# H7-Battery.net
KiCad netlist of a schematic drawn in Altium Designer
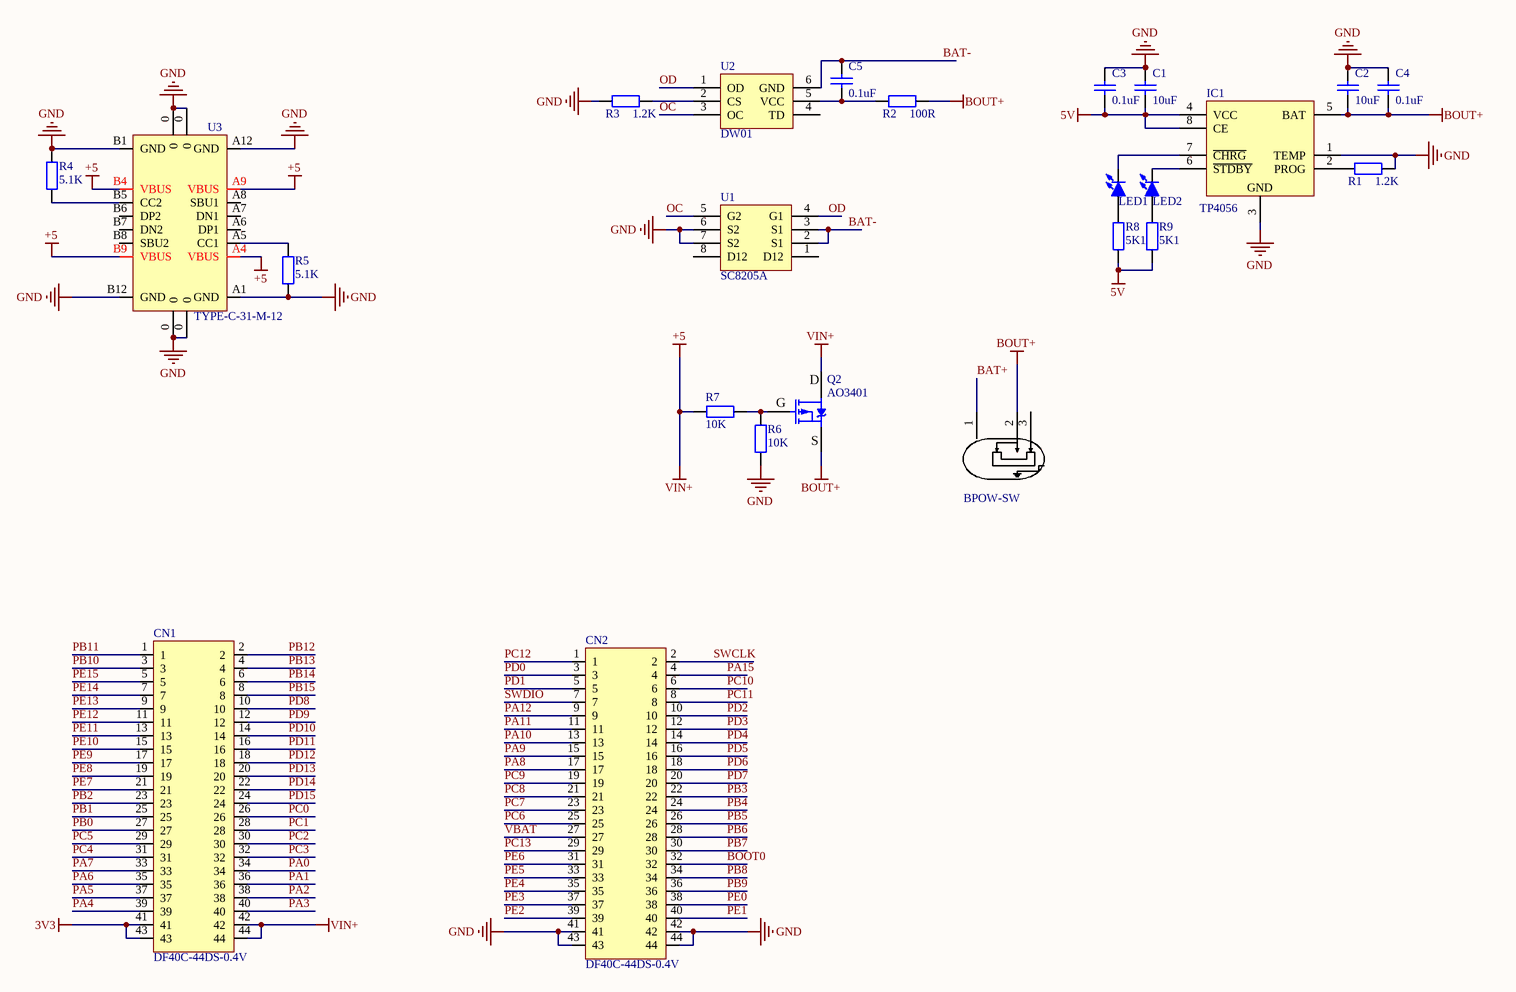
[diagram p0: H7-Battery.SchDoc]

(export (version "E")
  (design (tool "Eeschema 10.0.6"))
  (components
    (comp (ref "BPOW-SW")
      (value "MSK12C02")
      (footprint "SW-TH_MSK12C02")
      (fields (field (name "MANUFACTURER") "SHOU HAN(首韩)"))
      (libsource (lib "Pi") (part "MSK12C02"))
    )
    (comp (ref "C1")
      (value "10uF")
      (footprint "C0603_L")
      (description "贴片电容")
      (libsource (lib "0.1 - 电阻-电容-电感-电位器") (part "C"))
    )
    (comp (ref "C2")
      (value "10uF")
      (footprint "C0603_L")
      (description "贴片电容")
      (libsource (lib "0.1 - 电阻-电容-电感-电位器") (part "C"))
    )
    (comp (ref "C3")
      (value "0.1uF")
      (footprint "C0603_L")
      (description "贴片电容")
      (libsource (lib "0.1 - 电阻-电容-电感-电位器") (part "C"))
    )
    (comp (ref "C4")
      (value "0.1uF")
      (footprint "C0603_L")
      (description "贴片电容")
      (libsource (lib "0.1 - 电阻-电容-电感-电位器") (part "C"))
    )
    (comp (ref "C5")
      (value "0.1uF")
      (footprint "C0603_L")
      (description "贴片电容")
      (libsource (lib "0.1 - 电阻-电容-电感-电位器") (part "C"))
    )
    (comp (ref "CN1")
      (value "DF40C-44DS-0.4V")
      (footprint "DF40C-44DS-0.4V")
      (description "母座")
      (libsource (lib "Pi") (part "DF40C-44DS-0.4V"))
    )
    (comp (ref "CN2")
      (value "DF40C-44DS-0.4V")
      (footprint "DF40C-44DS-0.4V")
      (description "母座")
      (libsource (lib "Pi") (part "DF40C-44DS-0.4V"))
    )
    (comp (ref "IC1")
      (value "TP4056")
      (footprint "ESOP8_L")
      (description "锂电池充电管理")
      (libsource (lib "Pi") (part "TP4056"))
    )
    (comp (ref "LED1")
      (value "~")
      (footprint "LED0603_R")
      (description "贴片LED")
      (libsource (lib "0.3 - LED发光二极管") (part "LED-SMD"))
    )
    (comp (ref "LED2")
      (value "~")
      (footprint "LED0603_G")
      (description "贴片LED")
      (libsource (lib "0.3 - LED发光二极管") (part "LED-SMD"))
    )
    (comp (ref "Q2")
      (value "AO3401")
      (footprint "SOT23-3N")
      (description "P沟道 30V/4.2A")
      (libsource (lib "0.4 - 三极管-场效应管-可控硅") (part "AO3401"))
    )
    (comp (ref "R1")
      (value "1.2K")
      (footprint "R0603_L")
      (description "贴片电阻")
      (libsource (lib "0.1 - 电阻-电容-电感-电位器") (part "R"))
    )
    (comp (ref "R2")
      (value "100R")
      (footprint "R0603_L")
      (description "贴片电阻")
      (libsource (lib "0.1 - 电阻-电容-电感-电位器") (part "R"))
    )
    (comp (ref "R3")
      (value "1.2K")
      (footprint "R0603_L")
      (description "贴片电阻")
      (libsource (lib "0.1 - 电阻-电容-电感-电位器") (part "R"))
    )
    (comp (ref "R4")
      (value "5.1K")
      (footprint "R0603_L")
      (description "贴片电阻")
      (libsource (lib "0.1 - 电阻-电容-电感-电位器") (part "R"))
    )
    (comp (ref "R5")
      (value "5.1K")
      (footprint "R0603_L")
      (description "贴片电阻")
      (libsource (lib "0.1 - 电阻-电容-电感-电位器") (part "R"))
    )
    (comp (ref "R6")
      (value "10K")
      (footprint "R0603_L")
      (description "贴片电阻")
      (libsource (lib "0.1 - 电阻-电容-电感-电位器") (part "R"))
    )
    (comp (ref "R7")
      (value "10K")
      (footprint "R0603_L")
      (description "贴片电阻")
      (libsource (lib "0.1 - 电阻-电容-电感-电位器") (part "R"))
    )
    (comp (ref "R8")
      (value "5K1")
      (footprint "R0603_L")
      (description "贴片电阻")
      (libsource (lib "0.1 - 电阻-电容-电感-电位器") (part "R"))
    )
    (comp (ref "R9")
      (value "5K1")
      (footprint "R0603_L")
      (description "贴片电阻")
      (libsource (lib "0.1 - 电阻-电容-电感-电位器") (part "R"))
    )
    (comp (ref "U1")
      (value "SC8205A")
      (footprint "TSSOP8_L")
      (description "N沟道 6A/20V锂电池保护板用的MOS管")
      (libsource (lib "Pi") (part "SC8205A"))
    )
    (comp (ref "U2")
      (value "DW01")
      (footprint "SOT23-6L")
      (description "锂电池过流保护IC")
      (libsource (lib "Pi") (part "DW01"))
    )
    (comp (ref "U3")
      (value "TYPE-C-31-M-12")
      (footprint "TYPE-C-31-M-12")
      (libsource (lib "Pi") (part "TYPE-C-31-M-12"))
    )
  )
  (nets
    (net (code "1") (name "+5") (class "Default")
      (node (ref "CN1") (pin "42") (pinfunction "42_42") (pintype "passive"))
      (node (ref "CN1") (pin "44") (pinfunction "44_44") (pintype "passive"))
      (node (ref "Q2") (pin "3") (pinfunction "D_3") (pintype "passive"))
      (node (ref "R7") (pin "2") (pinfunction "2_2") (pintype "passive"))
      (node (ref "U3") (pin "A4") (pinfunction "VBUS_A4") (pintype "passive"))
      (node (ref "U3") (pin "A9") (pinfunction "VBUS_A9") (pintype "passive"))
      (node (ref "U3") (pin "B4") (pinfunction "VBUS_B4") (pintype "passive"))
      (node (ref "U3") (pin "B9") (pinfunction "VBUS_B9") (pintype "passive"))
    )
    (net (code "2") (name "/BAT+") (class "Default")
      (node (ref "BPOW-SW") (pin "1") (pinfunction "1_1") (pintype "passive"))
    )
    (net (code "3") (name "/BAT-") (class "Default")
      (node (ref "C5") (pin "2") (pinfunction "2_2") (pintype "passive"))
      (node (ref "U1") (pin "2") (pinfunction "S1_2") (pintype "passive"))
      (node (ref "U1") (pin "3") (pinfunction "S1_3") (pintype "passive"))
      (node (ref "U2") (pin "6") (pinfunction "GND_6") (pintype "passive"))
    )
    (net (code "4") (name "/BOOT0") (class "Default")
      (node (ref "CN2") (pin "32") (pinfunction "32_32") (pintype "passive"))
    )
    (net (code "5") (name "/OC") (class "Default")
      (node (ref "U1") (pin "5") (pinfunction "G2_5") (pintype "passive"))
      (node (ref "U2") (pin "3") (pinfunction "OC_3") (pintype "passive"))
    )
    (net (code "6") (name "/OD") (class "Default")
      (node (ref "U1") (pin "4") (pinfunction "G1_4") (pintype "passive"))
      (node (ref "U2") (pin "1") (pinfunction "OD_1") (pintype "passive"))
    )
    (net (code "7") (name "/PA0") (class "Default")
      (node (ref "CN1") (pin "34") (pinfunction "34_34") (pintype "passive"))
    )
    (net (code "8") (name "/PA1") (class "Default")
      (node (ref "CN1") (pin "36") (pinfunction "36_36") (pintype "passive"))
    )
    (net (code "9") (name "/PA2") (class "Default")
      (node (ref "CN1") (pin "38") (pinfunction "38_38") (pintype "passive"))
    )
    (net (code "10") (name "/PA3") (class "Default")
      (node (ref "CN1") (pin "40") (pinfunction "40_40") (pintype "passive"))
    )
    (net (code "11") (name "/PA4") (class "Default")
      (node (ref "CN1") (pin "39") (pinfunction "39_39") (pintype "passive"))
    )
    (net (code "12") (name "/PA5") (class "Default")
      (node (ref "CN1") (pin "37") (pinfunction "37_37") (pintype "passive"))
    )
    (net (code "13") (name "/PA6") (class "Default")
      (node (ref "CN1") (pin "35") (pinfunction "35_35") (pintype "passive"))
    )
    (net (code "14") (name "/PA7") (class "Default")
      (node (ref "CN1") (pin "33") (pinfunction "33_33") (pintype "passive"))
    )
    (net (code "15") (name "/PA8") (class "Default")
      (node (ref "CN2") (pin "17") (pinfunction "17_17") (pintype "passive"))
    )
    (net (code "16") (name "/PA9") (class "Default")
      (node (ref "CN2") (pin "15") (pinfunction "15_15") (pintype "passive"))
    )
    (net (code "17") (name "/PA10") (class "Default")
      (node (ref "CN2") (pin "13") (pinfunction "13_13") (pintype "passive"))
    )
    (net (code "18") (name "/PA11") (class "Default")
      (node (ref "CN2") (pin "11") (pinfunction "11_11") (pintype "passive"))
    )
    (net (code "19") (name "/PA12") (class "Default")
      (node (ref "CN2") (pin "9") (pinfunction "9_9") (pintype "passive"))
    )
    (net (code "20") (name "/PA15") (class "Default")
      (node (ref "CN2") (pin "4") (pinfunction "4_4") (pintype "passive"))
    )
    (net (code "21") (name "/PB0") (class "Default")
      (node (ref "CN1") (pin "27") (pinfunction "27_27") (pintype "passive"))
    )
    (net (code "22") (name "/PB1") (class "Default")
      (node (ref "CN1") (pin "25") (pinfunction "25_25") (pintype "passive"))
    )
    (net (code "23") (name "/PB2") (class "Default")
      (node (ref "CN1") (pin "23") (pinfunction "23_23") (pintype "passive"))
    )
    (net (code "24") (name "/PB3") (class "Default")
      (node (ref "CN2") (pin "22") (pinfunction "22_22") (pintype "passive"))
    )
    (net (code "25") (name "/PB4") (class "Default")
      (node (ref "CN2") (pin "24") (pinfunction "24_24") (pintype "passive"))
    )
    (net (code "26") (name "/PB5") (class "Default")
      (node (ref "CN2") (pin "26") (pinfunction "26_26") (pintype "passive"))
    )
    (net (code "27") (name "/PB6") (class "Default")
      (node (ref "CN2") (pin "28") (pinfunction "28_28") (pintype "passive"))
    )
    (net (code "28") (name "/PB7") (class "Default")
      (node (ref "CN2") (pin "30") (pinfunction "30_30") (pintype "passive"))
    )
    (net (code "29") (name "/PB8") (class "Default")
      (node (ref "CN2") (pin "34") (pinfunction "34_34") (pintype "passive"))
    )
    (net (code "30") (name "/PB9") (class "Default")
      (node (ref "CN2") (pin "36") (pinfunction "36_36") (pintype "passive"))
    )
    (net (code "31") (name "/PB10") (class "Default")
      (node (ref "CN1") (pin "3") (pinfunction "3_3") (pintype "passive"))
    )
    (net (code "32") (name "/PB11") (class "Default")
      (node (ref "CN1") (pin "1") (pinfunction "1_1") (pintype "passive"))
    )
    (net (code "33") (name "/PB12") (class "Default")
      (node (ref "CN1") (pin "2") (pinfunction "2_2") (pintype "passive"))
    )
    (net (code "34") (name "/PB13") (class "Default")
      (node (ref "CN1") (pin "4") (pinfunction "4_4") (pintype "passive"))
    )
    (net (code "35") (name "/PB14") (class "Default")
      (node (ref "CN1") (pin "6") (pinfunction "6_6") (pintype "passive"))
    )
    (net (code "36") (name "/PB15") (class "Default")
      (node (ref "CN1") (pin "8") (pinfunction "8_8") (pintype "passive"))
    )
    (net (code "37") (name "/PC0") (class "Default")
      (node (ref "CN1") (pin "26") (pinfunction "26_26") (pintype "passive"))
    )
    (net (code "38") (name "/PC1") (class "Default")
      (node (ref "CN1") (pin "28") (pinfunction "28_28") (pintype "passive"))
    )
    (net (code "39") (name "/PC2") (class "Default")
      (node (ref "CN1") (pin "30") (pinfunction "30_30") (pintype "passive"))
    )
    (net (code "40") (name "/PC3") (class "Default")
      (node (ref "CN1") (pin "32") (pinfunction "32_32") (pintype "passive"))
    )
    (net (code "41") (name "/PC4") (class "Default")
      (node (ref "CN1") (pin "31") (pinfunction "31_31") (pintype "passive"))
    )
    (net (code "42") (name "/PC5") (class "Default")
      (node (ref "CN1") (pin "29") (pinfunction "29_29") (pintype "passive"))
    )
    (net (code "43") (name "/PC6") (class "Default")
      (node (ref "CN2") (pin "25") (pinfunction "25_25") (pintype "passive"))
    )
    (net (code "44") (name "/PC7") (class "Default")
      (node (ref "CN2") (pin "23") (pinfunction "23_23") (pintype "passive"))
    )
    (net (code "45") (name "/PC8") (class "Default")
      (node (ref "CN2") (pin "21") (pinfunction "21_21") (pintype "passive"))
    )
    (net (code "46") (name "/PC9") (class "Default")
      (node (ref "CN2") (pin "19") (pinfunction "19_19") (pintype "passive"))
    )
    (net (code "47") (name "/PC10") (class "Default")
      (node (ref "CN2") (pin "6") (pinfunction "6_6") (pintype "passive"))
    )
    (net (code "48") (name "/PC11") (class "Default")
      (node (ref "CN2") (pin "8") (pinfunction "8_8") (pintype "passive"))
    )
    (net (code "49") (name "/PC12") (class "Default")
      (node (ref "CN2") (pin "1") (pinfunction "1_1") (pintype "passive"))
    )
    (net (code "50") (name "/PC13") (class "Default")
      (node (ref "CN2") (pin "29") (pinfunction "29_29") (pintype "passive"))
    )
    (net (code "51") (name "/PD0") (class "Default")
      (node (ref "CN2") (pin "3") (pinfunction "3_3") (pintype "passive"))
    )
    (net (code "52") (name "/PD1") (class "Default")
      (node (ref "CN2") (pin "5") (pinfunction "5_5") (pintype "passive"))
    )
    (net (code "53") (name "/PD2") (class "Default")
      (node (ref "CN2") (pin "10") (pinfunction "10_10") (pintype "passive"))
    )
    (net (code "54") (name "/PD3") (class "Default")
      (node (ref "CN2") (pin "12") (pinfunction "12_12") (pintype "passive"))
    )
    (net (code "55") (name "/PD4") (class "Default")
      (node (ref "CN2") (pin "14") (pinfunction "14_14") (pintype "passive"))
    )
    (net (code "56") (name "/PD5") (class "Default")
      (node (ref "CN2") (pin "16") (pinfunction "16_16") (pintype "passive"))
    )
    (net (code "57") (name "/PD6") (class "Default")
      (node (ref "CN2") (pin "18") (pinfunction "18_18") (pintype "passive"))
    )
    (net (code "58") (name "/PD7") (class "Default")
      (node (ref "CN2") (pin "20") (pinfunction "20_20") (pintype "passive"))
    )
    (net (code "59") (name "/PD8") (class "Default")
      (node (ref "CN1") (pin "10") (pinfunction "10_10") (pintype "passive"))
    )
    (net (code "60") (name "/PD9") (class "Default")
      (node (ref "CN1") (pin "12") (pinfunction "12_12") (pintype "passive"))
    )
    (net (code "61") (name "/PD10") (class "Default")
      (node (ref "CN1") (pin "14") (pinfunction "14_14") (pintype "passive"))
    )
    (net (code "62") (name "/PD11") (class "Default")
      (node (ref "CN1") (pin "16") (pinfunction "16_16") (pintype "passive"))
    )
    (net (code "63") (name "/PD12") (class "Default")
      (node (ref "CN1") (pin "18") (pinfunction "18_18") (pintype "passive"))
    )
    (net (code "64") (name "/PD13") (class "Default")
      (node (ref "CN1") (pin "20") (pinfunction "20_20") (pintype "passive"))
    )
    (net (code "65") (name "/PD14") (class "Default")
      (node (ref "CN1") (pin "22") (pinfunction "22_22") (pintype "passive"))
    )
    (net (code "66") (name "/PD15") (class "Default")
      (node (ref "CN1") (pin "24") (pinfunction "24_24") (pintype "passive"))
    )
    (net (code "67") (name "/PE0") (class "Default")
      (node (ref "CN2") (pin "38") (pinfunction "38_38") (pintype "passive"))
    )
    (net (code "68") (name "/PE1") (class "Default")
      (node (ref "CN2") (pin "40") (pinfunction "40_40") (pintype "passive"))
    )
    (net (code "69") (name "/PE2") (class "Default")
      (node (ref "CN2") (pin "39") (pinfunction "39_39") (pintype "passive"))
    )
    (net (code "70") (name "/PE3") (class "Default")
      (node (ref "CN2") (pin "37") (pinfunction "37_37") (pintype "passive"))
    )
    (net (code "71") (name "/PE4") (class "Default")
      (node (ref "CN2") (pin "35") (pinfunction "35_35") (pintype "passive"))
    )
    (net (code "72") (name "/PE5") (class "Default")
      (node (ref "CN2") (pin "33") (pinfunction "33_33") (pintype "passive"))
    )
    (net (code "73") (name "/PE6") (class "Default")
      (node (ref "CN2") (pin "31") (pinfunction "31_31") (pintype "passive"))
    )
    (net (code "74") (name "/PE7") (class "Default")
      (node (ref "CN1") (pin "21") (pinfunction "21_21") (pintype "passive"))
    )
    (net (code "75") (name "/PE8") (class "Default")
      (node (ref "CN1") (pin "19") (pinfunction "19_19") (pintype "passive"))
    )
    (net (code "76") (name "/PE9") (class "Default")
      (node (ref "CN1") (pin "17") (pinfunction "17_17") (pintype "passive"))
    )
    (net (code "77") (name "/PE10") (class "Default")
      (node (ref "CN1") (pin "15") (pinfunction "15_15") (pintype "passive"))
    )
    (net (code "78") (name "/PE11") (class "Default")
      (node (ref "CN1") (pin "13") (pinfunction "13_13") (pintype "passive"))
    )
    (net (code "79") (name "/PE12") (class "Default")
      (node (ref "CN1") (pin "11") (pinfunction "11_11") (pintype "passive"))
    )
    (net (code "80") (name "/PE13") (class "Default")
      (node (ref "CN1") (pin "9") (pinfunction "9_9") (pintype "passive"))
    )
    (net (code "81") (name "/PE14") (class "Default")
      (node (ref "CN1") (pin "7") (pinfunction "7_7") (pintype "passive"))
    )
    (net (code "82") (name "/PE15") (class "Default")
      (node (ref "CN1") (pin "5") (pinfunction "5_5") (pintype "passive"))
    )
    (net (code "83") (name "/SWCLK") (class "Default")
      (node (ref "CN2") (pin "2") (pinfunction "2_2") (pintype "passive"))
    )
    (net (code "84") (name "/SWDIO") (class "Default")
      (node (ref "CN2") (pin "7") (pinfunction "7_7") (pintype "passive"))
    )
    (net (code "85") (name "/VBAT") (class "Default")
      (node (ref "CN2") (pin "27") (pinfunction "27_27") (pintype "passive"))
    )
    (net (code "86") (name "3V3") (class "Default")
      (node (ref "CN1") (pin "41") (pinfunction "41_41") (pintype "passive"))
      (node (ref "CN1") (pin "43") (pinfunction "43_43") (pintype "passive"))
    )
    (net (code "87") (name "5V") (class "Default")
      (node (ref "C1") (pin "1") (pinfunction "1_1") (pintype "passive"))
      (node (ref "C3") (pin "1") (pinfunction "1_1") (pintype "passive"))
      (node (ref "IC1") (pin "4") (pinfunction "VCC_4") (pintype "passive"))
      (node (ref "IC1") (pin "8") (pinfunction "CE_8") (pintype "passive"))
      (node (ref "R8") (pin "1") (pinfunction "1_1") (pintype "passive"))
      (node (ref "R9") (pin "1") (pinfunction "1_1") (pintype "passive"))
    )
    (net (code "88") (name "BOUT+") (class "Default")
      (node (ref "BPOW-SW") (pin "2") (pinfunction "2_2") (pintype "passive"))
      (node (ref "C2") (pin "1") (pinfunction "1_1") (pintype "passive"))
      (node (ref "C4") (pin "1") (pinfunction "1_1") (pintype "passive"))
      (node (ref "IC1") (pin "5") (pinfunction "BAT_5") (pintype "passive"))
      (node (ref "Q2") (pin "2") (pinfunction "S_2") (pintype "passive"))
      (node (ref "R2") (pin "2") (pinfunction "2_2") (pintype "passive"))
    )
    (net (code "89") (name "GND") (class "Default")
      (node (ref "C1") (pin "2") (pinfunction "2_2") (pintype "passive"))
      (node (ref "C2") (pin "2") (pinfunction "2_2") (pintype "passive"))
      (node (ref "C3") (pin "2") (pinfunction "2_2") (pintype "passive"))
      (node (ref "C4") (pin "2") (pinfunction "2_2") (pintype "passive"))
      (node (ref "CN2") (pin "41") (pinfunction "41_41") (pintype "passive"))
      (node (ref "CN2") (pin "42") (pinfunction "42_42") (pintype "passive"))
      (node (ref "CN2") (pin "43") (pinfunction "43_43") (pintype "passive"))
      (node (ref "CN2") (pin "44") (pinfunction "44_44") (pintype "passive"))
      (node (ref "IC1") (pin "1") (pinfunction "TEMP_1") (pintype "passive"))
      (node (ref "IC1") (pin "3") (pinfunction "GND_3") (pintype "passive"))
      (node (ref "R1") (pin "2") (pinfunction "2_2") (pintype "passive"))
      (node (ref "R3") (pin "1") (pinfunction "1_1") (pintype "passive"))
      (node (ref "R4") (pin "2") (pinfunction "2_2") (pintype "passive"))
      (node (ref "R5") (pin "1") (pinfunction "1_1") (pintype "passive"))
      (node (ref "R6") (pin "1") (pinfunction "1_1") (pintype "passive"))
      (node (ref "U1") (pin "6") (pinfunction "S2_6") (pintype "passive"))
      (node (ref "U1") (pin "7") (pinfunction "S2_7") (pintype "passive"))
      (node (ref "U3") (pin "0") (pinfunction "0_0") (pintype "passive"))
      (node (ref "U3") (pin "A1") (pinfunction "GND_A1") (pintype "passive"))
      (node (ref "U3") (pin "A12") (pinfunction "GND_A12") (pintype "passive"))
      (node (ref "U3") (pin "B1") (pinfunction "GND_B1") (pintype "passive"))
      (node (ref "U3") (pin "B12") (pinfunction "GND_B12") (pintype "passive"))
    )
    (net (code "90") (name "Net-(IC1-PROG)") (class "Default")
      (node (ref "IC1") (pin "2") (pinfunction "PROG_2") (pintype "passive"))
      (node (ref "R1") (pin "1") (pinfunction "1_1") (pintype "passive"))
    )
    (net (code "91") (name "Net-(IC1-~{CHRG})") (class "Default")
      (node (ref "IC1") (pin "7") (pinfunction "~{CHRG}_7") (pintype "passive"))
      (node (ref "LED1") (pin "2") (pinfunction "K_2") (pintype "passive"))
    )
    (net (code "92") (name "Net-(IC1-~{STDBY})") (class "Default")
      (node (ref "IC1") (pin "6") (pinfunction "~{STDBY}_6") (pintype "passive"))
      (node (ref "LED2") (pin "2") (pinfunction "K_2") (pintype "passive"))
    )
    (net (code "93") (name "Net-(LED1-A)") (class "Default")
      (node (ref "LED1") (pin "1") (pinfunction "A_1") (pintype "passive"))
      (node (ref "R8") (pin "2") (pinfunction "2_2") (pintype "passive"))
    )
    (net (code "94") (name "Net-(LED2-A)") (class "Default")
      (node (ref "LED2") (pin "1") (pinfunction "A_1") (pintype "passive"))
      (node (ref "R9") (pin "2") (pinfunction "2_2") (pintype "passive"))
    )
    (net (code "95") (name "Net-(Q2-G)") (class "Default")
      (node (ref "Q2") (pin "1") (pinfunction "G_1") (pintype "passive"))
      (node (ref "R6") (pin "2") (pinfunction "2_2") (pintype "passive"))
      (node (ref "R7") (pin "1") (pinfunction "1_1") (pintype "passive"))
    )
    (net (code "96") (name "Net-(U2-CS)") (class "Default")
      (node (ref "R3") (pin "2") (pinfunction "2_2") (pintype "passive"))
      (node (ref "U2") (pin "2") (pinfunction "CS_2") (pintype "passive"))
    )
    (net (code "97") (name "Net-(U2-VCC)") (class "Default")
      (node (ref "C5") (pin "1") (pinfunction "1_1") (pintype "passive"))
      (node (ref "R2") (pin "1") (pinfunction "1_1") (pintype "passive"))
      (node (ref "U2") (pin "5") (pinfunction "VCC_5") (pintype "passive"))
    )
    (net (code "98") (name "Net-(U3-CC1)") (class "Default")
      (node (ref "R5") (pin "2") (pinfunction "2_2") (pintype "passive"))
      (node (ref "U3") (pin "A5") (pinfunction "CC1_A5") (pintype "passive"))
    )
    (net (code "99") (name "Net-(U3-CC2)") (class "Default")
      (node (ref "R4") (pin "1") (pinfunction "1_1") (pintype "passive"))
      (node (ref "U3") (pin "B5") (pinfunction "CC2_B5") (pintype "passive"))
    )
    (net (code "100") (name "unconnected-(BPOW-SW-Pad3)") (class "Default")
      (node (ref "BPOW-SW") (pin "3") (pinfunction "3_3") (pintype "passive"))
    )
    (net (code "101") (name "unconnected-(U1-D12-Pad1)") (class "Default")
      (node (ref "U1") (pin "1") (pinfunction "D12_1") (pintype "passive"))
    )
    (net (code "102") (name "unconnected-(U1-D12-Pad8)") (class "Default")
      (node (ref "U1") (pin "8") (pinfunction "D12_8") (pintype "passive"))
    )
    (net (code "103") (name "unconnected-(U2-TD-Pad4)") (class "Default")
      (node (ref "U2") (pin "4") (pinfunction "TD_4") (pintype "passive"))
    )
    (net (code "104") (name "unconnected-(U3-DN1-PadA7)") (class "Default")
      (node (ref "U3") (pin "A7") (pinfunction "DN1_A7") (pintype "passive"))
    )
    (net (code "105") (name "unconnected-(U3-DN2-PadB7)") (class "Default")
      (node (ref "U3") (pin "B7") (pinfunction "DN2_B7") (pintype "passive"))
    )
    (net (code "106") (name "unconnected-(U3-DP1-PadA6)") (class "Default")
      (node (ref "U3") (pin "A6") (pinfunction "DP1_A6") (pintype "passive"))
    )
    (net (code "107") (name "unconnected-(U3-DP2-PadB6)") (class "Default")
      (node (ref "U3") (pin "B6") (pinfunction "DP2_B6") (pintype "passive"))
    )
    (net (code "108") (name "unconnected-(U3-SBU1-PadA8)") (class "Default")
      (node (ref "U3") (pin "A8") (pinfunction "SBU1_A8") (pintype "passive"))
    )
    (net (code "109") (name "unconnected-(U3-SBU2-PadB8)") (class "Default")
      (node (ref "U3") (pin "B8") (pinfunction "SBU2_B8") (pintype "passive"))
    )
  )
)
